# M253X.net
KiCad netlist of a schematic drawn in EAGLE
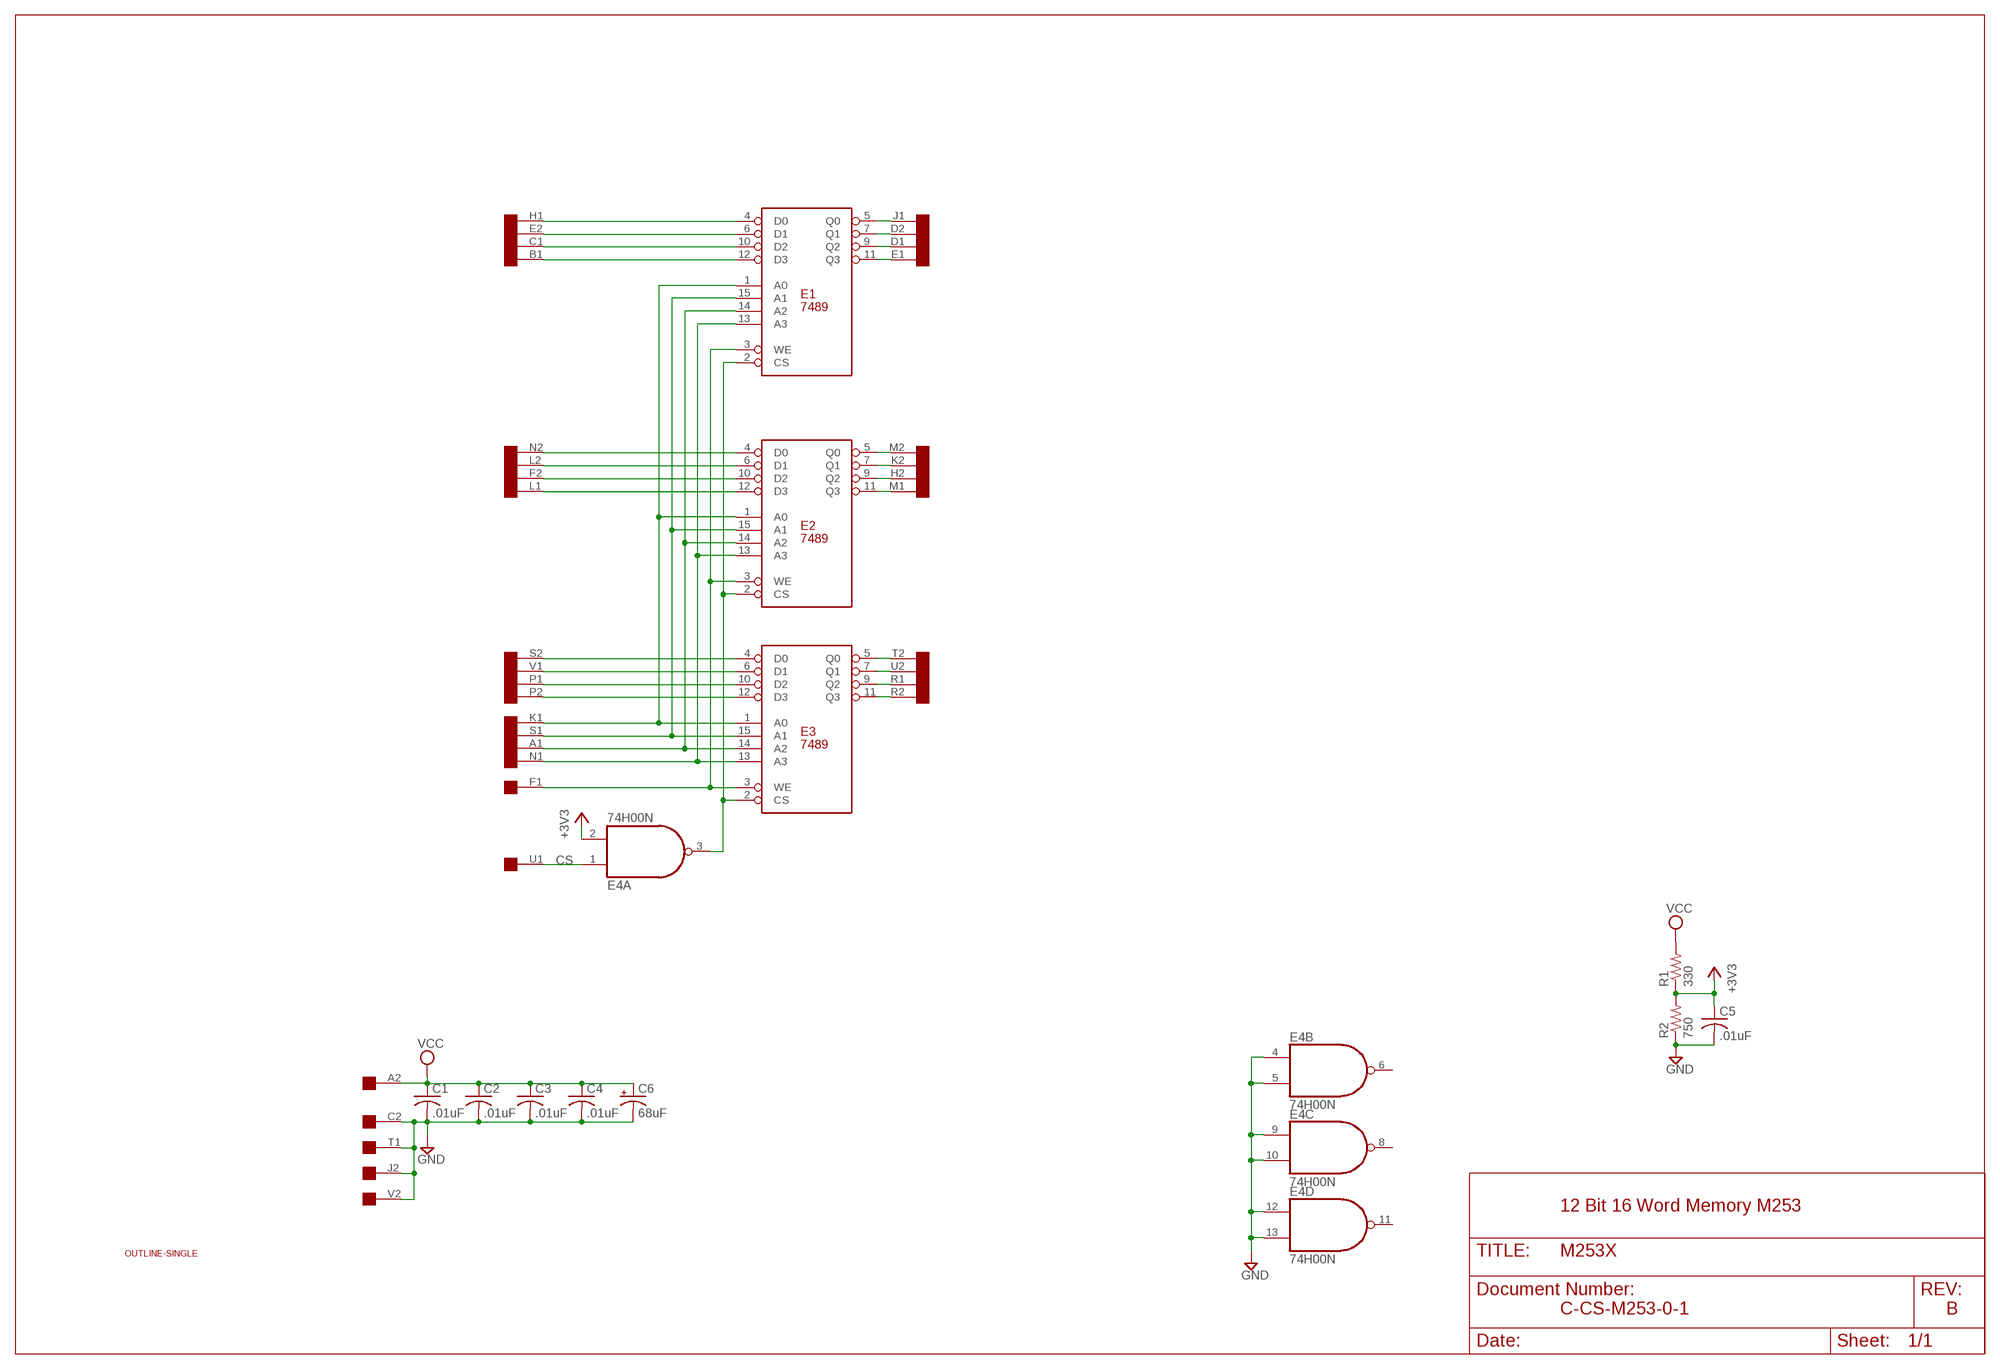
[diagram p0: schematic, sheet 1]

(export (version "E")
  (design (tool "Eeschema 10.0.6"))
  (components
    (comp (ref "C1")
      (value ".01uF")
      (footprint "eagle-import:C050-025X075")
      (libsource (lib "eagle-import") (part "C-US050-025X075"))
    )
    (comp (ref "C2")
      (value ".01uF")
      (footprint "eagle-import:C050-025X075")
      (libsource (lib "eagle-import") (part "C-US050-025X075"))
    )
    (comp (ref "C3")
      (value ".01uF")
      (footprint "eagle-import:C050-025X075")
      (libsource (lib "eagle-import") (part "C-US050-025X075"))
    )
    (comp (ref "C4")
      (value ".01uF")
      (footprint "eagle-import:C050-025X075")
      (libsource (lib "eagle-import") (part "C-US050-025X075"))
    )
    (comp (ref "C5")
      (value ".01uF")
      (footprint "eagle-import:C050-025X075")
      (libsource (lib "eagle-import") (part "C-US050-025X075"))
    )
    (comp (ref "C6")
      (value "68uF")
      (footprint "eagle-import:E25-9")
      (libsource (lib "eagle-import") (part "CPOL-USE25-9AXIAL"))
    )
    (comp (ref "E1")
      (value "7489")
      (footprint "eagle-import:DIL16")
      (libsource (lib "eagle-import") (part "7489"))
    )
    (comp (ref "E2")
      (value "7489")
      (footprint "eagle-import:DIL16")
      (libsource (lib "eagle-import") (part "7489"))
    )
    (comp (ref "E3")
      (value "7489")
      (footprint "eagle-import:DIL16")
      (libsource (lib "eagle-import") (part "7489"))
    )
    (comp (ref "E4")
      (value "74H00N")
      (footprint "eagle-import:DIL14")
      (libsource (lib "eagle-import") (part "7400NS"))
    )
    (comp (ref "R1")
      (value "330")
      (footprint "eagle-import:0207_10")
      (libsource (lib "eagle-import") (part "R-US_0207/10"))
    )
    (comp (ref "R2")
      (value "750")
      (footprint "eagle-import:0207_10")
      (libsource (lib "eagle-import") (part "R-US_0207/10"))
    )
    (comp (ref "U$1")
      (value "OUTLINE-SINGLE")
      (footprint "eagle-import:SINGLE")
      (libsource (lib "eagle-import") (part "OUTLINE-SINGLE"))
    )
    (comp (ref "U$2")
      (value "SINGLE")
      (footprint "eagle-import:EDGE-CON2")
      (libsource (lib "eagle-import") (part "SINGLE"))
    )
  )
  (nets
    (net (code "1") (name "+3V3") (class "Default")
      (node (ref "C5") (pin "1") (pinfunction "1_1") (pintype "passive"))
      (node (ref "E4") (pin "2") (pinfunction "I1_2") (pintype "input"))
      (node (ref "R1") (pin "1") (pinfunction "1_1") (pintype "passive"))
      (node (ref "R2") (pin "2") (pinfunction "2_2") (pintype "passive"))
    )
    (net (code "2") (name "/CS") (class "Default")
      (node (ref "E4") (pin "1") (pinfunction "I0_1") (pintype "input"))
      (node (ref "U$2") (pin "U1") (pinfunction "1_U1") (pintype "bidirectional"))
    )
    (net (code "3") (name "GND") (class "Default")
      (node (ref "C1") (pin "2") (pinfunction "2_2") (pintype "passive"))
      (node (ref "C2") (pin "2") (pinfunction "2_2") (pintype "passive"))
      (node (ref "C3") (pin "2") (pinfunction "2_2") (pintype "passive"))
      (node (ref "C4") (pin "2") (pinfunction "2_2") (pintype "passive"))
      (node (ref "C5") (pin "2") (pinfunction "2_2") (pintype "passive"))
      (node (ref "C6") (pin "-") (pinfunction "-_-") (pintype "passive"))
      (node (ref "E4") (pin "10") (pinfunction "I1_10") (pintype "input"))
      (node (ref "E4") (pin "12") (pinfunction "I0_12") (pintype "input"))
      (node (ref "E4") (pin "13") (pinfunction "I1_13") (pintype "input"))
      (node (ref "E4") (pin "4") (pinfunction "I0_4") (pintype "input"))
      (node (ref "E4") (pin "5") (pinfunction "I1_5") (pintype "input"))
      (node (ref "E4") (pin "9") (pinfunction "I0_9") (pintype "input"))
      (node (ref "R2") (pin "1") (pinfunction "1_1") (pintype "passive"))
      (node (ref "U$2") (pin "C2") (pinfunction "1_C2") (pintype "bidirectional"))
      (node (ref "U$2") (pin "J2") (pinfunction "1_J2") (pintype "bidirectional"))
      (node (ref "U$2") (pin "T1") (pinfunction "1_T1") (pintype "bidirectional"))
      (node (ref "U$2") (pin "V2") (pinfunction "1_V2") (pintype "bidirectional"))
    )
    (net (code "4") (name "Net-(E1A-A0)") (class "Default")
      (node (ref "E1") (pin "1") (pinfunction "A0_1") (pintype "input"))
      (node (ref "E2") (pin "1") (pinfunction "A0_1") (pintype "input"))
      (node (ref "E3") (pin "1") (pinfunction "A0_1") (pintype "input"))
      (node (ref "U$2") (pin "K1") (pinfunction "1_K1") (pintype "bidirectional"))
    )
    (net (code "5") (name "Net-(E1A-A1)") (class "Default")
      (node (ref "E1") (pin "15") (pinfunction "A1_15") (pintype "input"))
      (node (ref "E2") (pin "15") (pinfunction "A1_15") (pintype "input"))
      (node (ref "E3") (pin "15") (pinfunction "A1_15") (pintype "input"))
      (node (ref "U$2") (pin "S1") (pinfunction "1_S1") (pintype "bidirectional"))
    )
    (net (code "6") (name "Net-(E1A-A2)") (class "Default")
      (node (ref "E1") (pin "14") (pinfunction "A2_14") (pintype "input"))
      (node (ref "E2") (pin "14") (pinfunction "A2_14") (pintype "input"))
      (node (ref "E3") (pin "14") (pinfunction "A2_14") (pintype "input"))
      (node (ref "U$2") (pin "A1") (pinfunction "1_A1") (pintype "bidirectional"))
    )
    (net (code "7") (name "Net-(E1A-A3)") (class "Default")
      (node (ref "E1") (pin "13") (pinfunction "A3_13") (pintype "input"))
      (node (ref "E2") (pin "13") (pinfunction "A3_13") (pintype "input"))
      (node (ref "E3") (pin "13") (pinfunction "A3_13") (pintype "input"))
      (node (ref "U$2") (pin "N1") (pinfunction "1_N1") (pintype "bidirectional"))
    )
    (net (code "8") (name "Net-(E1A-CS)") (class "Default")
      (node (ref "E1") (pin "2") (pinfunction "CS_2") (pintype "input"))
      (node (ref "E2") (pin "2") (pinfunction "CS_2") (pintype "input"))
      (node (ref "E3") (pin "2") (pinfunction "CS_2") (pintype "input"))
      (node (ref "E4") (pin "3") (pinfunction "O_3") (pintype "output"))
    )
    (net (code "9") (name "Net-(E1A-D0)") (class "Default")
      (node (ref "E1") (pin "4") (pinfunction "D0_4") (pintype "input"))
      (node (ref "U$2") (pin "H1") (pinfunction "1_H1") (pintype "bidirectional"))
    )
    (net (code "10") (name "Net-(E1A-D1)") (class "Default")
      (node (ref "E1") (pin "6") (pinfunction "D1_6") (pintype "input"))
      (node (ref "U$2") (pin "E2") (pinfunction "1_E2") (pintype "bidirectional"))
    )
    (net (code "11") (name "Net-(E1A-D2)") (class "Default")
      (node (ref "E1") (pin "10") (pinfunction "D2_10") (pintype "input"))
      (node (ref "U$2") (pin "C1") (pinfunction "1_C1") (pintype "bidirectional"))
    )
    (net (code "12") (name "Net-(E1A-D3)") (class "Default")
      (node (ref "E1") (pin "12") (pinfunction "D3_12") (pintype "input"))
      (node (ref "U$2") (pin "B1") (pinfunction "1_B1") (pintype "bidirectional"))
    )
    (net (code "13") (name "Net-(E1A-Q0)") (class "Default")
      (node (ref "E1") (pin "5") (pinfunction "Q0_5") (pintype "output"))
      (node (ref "U$2") (pin "J1") (pinfunction "1_J1") (pintype "bidirectional"))
    )
    (net (code "14") (name "Net-(E1A-Q1)") (class "Default")
      (node (ref "E1") (pin "7") (pinfunction "Q1_7") (pintype "output"))
      (node (ref "U$2") (pin "D2") (pinfunction "1_D2") (pintype "bidirectional"))
    )
    (net (code "15") (name "Net-(E1A-Q2)") (class "Default")
      (node (ref "E1") (pin "9") (pinfunction "Q2_9") (pintype "output"))
      (node (ref "U$2") (pin "D1") (pinfunction "1_D1") (pintype "bidirectional"))
    )
    (net (code "16") (name "Net-(E1A-Q3)") (class "Default")
      (node (ref "E1") (pin "11") (pinfunction "Q3_11") (pintype "output"))
      (node (ref "U$2") (pin "E1") (pinfunction "1_E1") (pintype "bidirectional"))
    )
    (net (code "17") (name "Net-(E1A-WE)") (class "Default")
      (node (ref "E1") (pin "3") (pinfunction "WE_3") (pintype "input"))
      (node (ref "E2") (pin "3") (pinfunction "WE_3") (pintype "input"))
      (node (ref "E3") (pin "3") (pinfunction "WE_3") (pintype "input"))
      (node (ref "U$2") (pin "F1") (pinfunction "1_F1") (pintype "bidirectional"))
    )
    (net (code "18") (name "Net-(E2A-D0)") (class "Default")
      (node (ref "E2") (pin "4") (pinfunction "D0_4") (pintype "input"))
      (node (ref "U$2") (pin "N2") (pinfunction "1_N2") (pintype "bidirectional"))
    )
    (net (code "19") (name "Net-(E2A-D1)") (class "Default")
      (node (ref "E2") (pin "6") (pinfunction "D1_6") (pintype "input"))
      (node (ref "U$2") (pin "L2") (pinfunction "1_L2") (pintype "bidirectional"))
    )
    (net (code "20") (name "Net-(E2A-D2)") (class "Default")
      (node (ref "E2") (pin "10") (pinfunction "D2_10") (pintype "input"))
      (node (ref "U$2") (pin "F2") (pinfunction "1_F2") (pintype "bidirectional"))
    )
    (net (code "21") (name "Net-(E2A-D3)") (class "Default")
      (node (ref "E2") (pin "12") (pinfunction "D3_12") (pintype "input"))
      (node (ref "U$2") (pin "L1") (pinfunction "1_L1") (pintype "bidirectional"))
    )
    (net (code "22") (name "Net-(E2A-Q0)") (class "Default")
      (node (ref "E2") (pin "5") (pinfunction "Q0_5") (pintype "output"))
      (node (ref "U$2") (pin "M2") (pinfunction "1_M2") (pintype "bidirectional"))
    )
    (net (code "23") (name "Net-(E2A-Q1)") (class "Default")
      (node (ref "E2") (pin "7") (pinfunction "Q1_7") (pintype "output"))
      (node (ref "U$2") (pin "K2") (pinfunction "1_K2") (pintype "bidirectional"))
    )
    (net (code "24") (name "Net-(E2A-Q2)") (class "Default")
      (node (ref "E2") (pin "9") (pinfunction "Q2_9") (pintype "output"))
      (node (ref "U$2") (pin "H2") (pinfunction "1_H2") (pintype "bidirectional"))
    )
    (net (code "25") (name "Net-(E2A-Q3)") (class "Default")
      (node (ref "E2") (pin "11") (pinfunction "Q3_11") (pintype "output"))
      (node (ref "U$2") (pin "M1") (pinfunction "1_M1") (pintype "bidirectional"))
    )
    (net (code "26") (name "Net-(E3A-D0)") (class "Default")
      (node (ref "E3") (pin "4") (pinfunction "D0_4") (pintype "input"))
      (node (ref "U$2") (pin "S2") (pinfunction "1_S2") (pintype "bidirectional"))
    )
    (net (code "27") (name "Net-(E3A-D1)") (class "Default")
      (node (ref "E3") (pin "6") (pinfunction "D1_6") (pintype "input"))
      (node (ref "U$2") (pin "V1") (pinfunction "1_V1") (pintype "bidirectional"))
    )
    (net (code "28") (name "Net-(E3A-D2)") (class "Default")
      (node (ref "E3") (pin "10") (pinfunction "D2_10") (pintype "input"))
      (node (ref "U$2") (pin "P1") (pinfunction "1_P1") (pintype "bidirectional"))
    )
    (net (code "29") (name "Net-(E3A-D3)") (class "Default")
      (node (ref "E3") (pin "12") (pinfunction "D3_12") (pintype "input"))
      (node (ref "U$2") (pin "P2") (pinfunction "1_P2") (pintype "bidirectional"))
    )
    (net (code "30") (name "Net-(E3A-Q0)") (class "Default")
      (node (ref "E3") (pin "5") (pinfunction "Q0_5") (pintype "output"))
      (node (ref "U$2") (pin "T2") (pinfunction "1_T2") (pintype "bidirectional"))
    )
    (net (code "31") (name "Net-(E3A-Q1)") (class "Default")
      (node (ref "E3") (pin "7") (pinfunction "Q1_7") (pintype "output"))
      (node (ref "U$2") (pin "U2") (pinfunction "1_U2") (pintype "bidirectional"))
    )
    (net (code "32") (name "Net-(E3A-Q2)") (class "Default")
      (node (ref "E3") (pin "9") (pinfunction "Q2_9") (pintype "output"))
      (node (ref "U$2") (pin "R1") (pinfunction "1_R1") (pintype "bidirectional"))
    )
    (net (code "33") (name "Net-(E3A-Q3)") (class "Default")
      (node (ref "E3") (pin "11") (pinfunction "Q3_11") (pintype "output"))
      (node (ref "U$2") (pin "R2") (pinfunction "1_R2") (pintype "bidirectional"))
    )
    (net (code "34") (name "VCC") (class "Default")
      (node (ref "C1") (pin "1") (pinfunction "1_1") (pintype "passive"))
      (node (ref "C2") (pin "1") (pinfunction "1_1") (pintype "passive"))
      (node (ref "C3") (pin "1") (pinfunction "1_1") (pintype "passive"))
      (node (ref "C4") (pin "1") (pinfunction "1_1") (pintype "passive"))
      (node (ref "C6") (pin "+") (pinfunction "+_+") (pintype "passive"))
      (node (ref "R1") (pin "2") (pinfunction "2_2") (pintype "passive"))
      (node (ref "U$2") (pin "A2") (pinfunction "1_A2") (pintype "bidirectional"))
    )
    (net (code "35") (name "unconnected-(E4B-O-Pad6)") (class "Default")
      (node (ref "E4") (pin "6") (pinfunction "O_6") (pintype "output"))
    )
    (net (code "36") (name "unconnected-(E4C-O-Pad8)") (class "Default")
      (node (ref "E4") (pin "8") (pinfunction "O_8") (pintype "output"))
    )
    (net (code "37") (name "unconnected-(E4D-O-Pad11)") (class "Default")
      (node (ref "E4") (pin "11") (pinfunction "O_11") (pintype "output"))
    )
  )
)
